# Tractor2000.net
KiCad netlist of a schematic drawn in Altium Designer
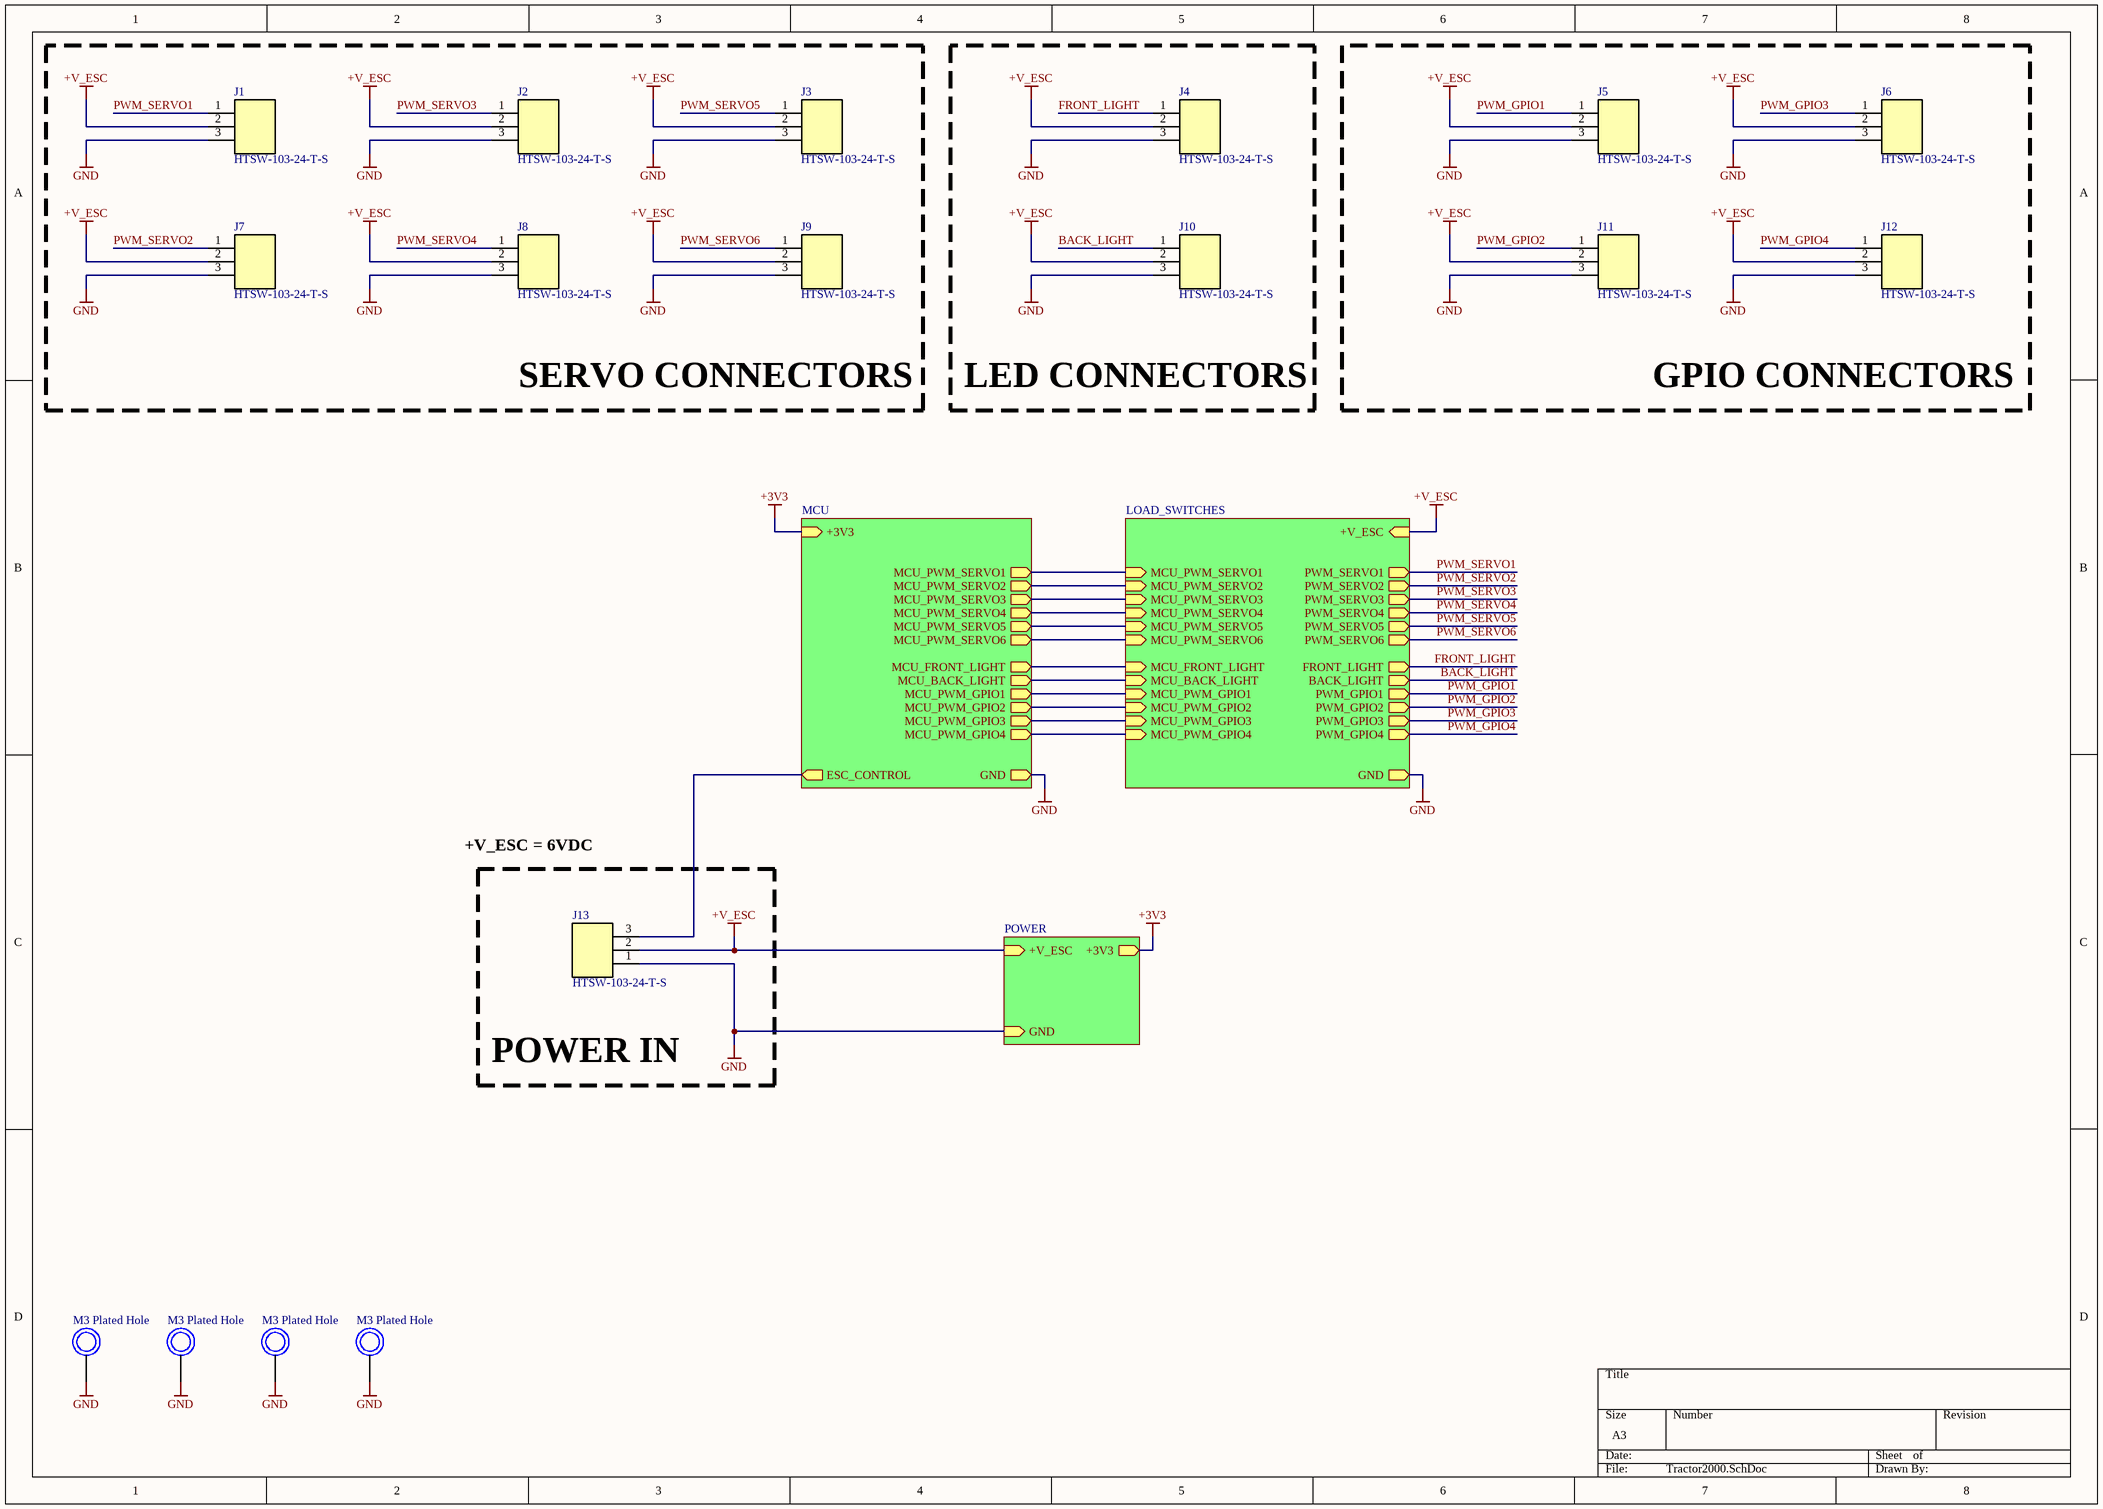
[diagram p0: Tractor2000.SchDoc]

(export (version "E")
  (design (tool "Eeschema 10.0.6"))
  (components
    (comp (ref "J1")
      (value "HTSW-103-24-T-S")
      (footprint "CON3_1X3_TU_TSW_SAI")
      (description "Description")
      (fields (field (name "COPYRIGHT") "Copyright (C) 2026 Ultra Librarian. All rights reserved."))
      (libsource (lib "Tractor2000") (part "HTSW-103-24-T-S"))
    )
    (comp (ref "J2")
      (value "HTSW-103-24-T-S")
      (footprint "CON3_1X3_TU_TSW_SAI")
      (description "Description")
      (fields (field (name "COPYRIGHT") "Copyright (C) 2026 Ultra Librarian. All rights reserved."))
      (libsource (lib "Tractor2000") (part "HTSW-103-24-T-S"))
    )
    (comp (ref "J3")
      (value "HTSW-103-24-T-S")
      (footprint "CON3_1X3_TU_TSW_SAI")
      (description "Description")
      (fields (field (name "COPYRIGHT") "Copyright (C) 2026 Ultra Librarian. All rights reserved."))
      (libsource (lib "Tractor2000") (part "HTSW-103-24-T-S"))
    )
    (comp (ref "J4")
      (value "HTSW-103-24-T-S")
      (footprint "CON3_1X3_TU_TSW_SAI")
      (description "Description")
      (fields (field (name "COPYRIGHT") "Copyright (C) 2026 Ultra Librarian. All rights reserved."))
      (libsource (lib "Tractor2000") (part "HTSW-103-24-T-S"))
    )
    (comp (ref "J5")
      (value "HTSW-103-24-T-S")
      (footprint "CON3_1X3_TU_TSW_SAI")
      (description "Description")
      (fields (field (name "COPYRIGHT") "Copyright (C) 2026 Ultra Librarian. All rights reserved."))
      (libsource (lib "Tractor2000") (part "HTSW-103-24-T-S"))
    )
    (comp (ref "J6")
      (value "HTSW-103-24-T-S")
      (footprint "CON3_1X3_TU_TSW_SAI")
      (description "Description")
      (fields (field (name "COPYRIGHT") "Copyright (C) 2026 Ultra Librarian. All rights reserved."))
      (libsource (lib "Tractor2000") (part "HTSW-103-24-T-S"))
    )
    (comp (ref "J7")
      (value "HTSW-103-24-T-S")
      (footprint "CON3_1X3_TU_TSW_SAI")
      (description "Description")
      (fields (field (name "COPYRIGHT") "Copyright (C) 2026 Ultra Librarian. All rights reserved."))
      (libsource (lib "Tractor2000") (part "HTSW-103-24-T-S"))
    )
    (comp (ref "J8")
      (value "HTSW-103-24-T-S")
      (footprint "CON3_1X3_TU_TSW_SAI")
      (description "Description")
      (fields (field (name "COPYRIGHT") "Copyright (C) 2026 Ultra Librarian. All rights reserved."))
      (libsource (lib "Tractor2000") (part "HTSW-103-24-T-S"))
    )
    (comp (ref "J9")
      (value "HTSW-103-24-T-S")
      (footprint "CON3_1X3_TU_TSW_SAI")
      (description "Description")
      (fields (field (name "COPYRIGHT") "Copyright (C) 2026 Ultra Librarian. All rights reserved."))
      (libsource (lib "Tractor2000") (part "HTSW-103-24-T-S"))
    )
    (comp (ref "J10")
      (value "HTSW-103-24-T-S")
      (footprint "CON3_1X3_TU_TSW_SAI")
      (description "Description")
      (fields (field (name "COPYRIGHT") "Copyright (C) 2026 Ultra Librarian. All rights reserved."))
      (libsource (lib "Tractor2000") (part "HTSW-103-24-T-S"))
    )
    (comp (ref "J11")
      (value "HTSW-103-24-T-S")
      (footprint "CON3_1X3_TU_TSW_SAI")
      (description "Description")
      (fields (field (name "COPYRIGHT") "Copyright (C) 2026 Ultra Librarian. All rights reserved."))
      (libsource (lib "Tractor2000") (part "HTSW-103-24-T-S"))
    )
    (comp (ref "J12")
      (value "HTSW-103-24-T-S")
      (footprint "CON3_1X3_TU_TSW_SAI")
      (description "Description")
      (fields (field (name "COPYRIGHT") "Copyright (C) 2026 Ultra Librarian. All rights reserved."))
      (libsource (lib "Tractor2000") (part "HTSW-103-24-T-S"))
    )
    (comp (ref "J13")
      (value "HTSW-103-24-T-S")
      (footprint "CON3_1X3_TU_TSW_SAI")
      (description "Description")
      (fields (field (name "COPYRIGHT") "Copyright (C) 2026 Ultra Librarian. All rights reserved."))
      (libsource (lib "") (part "HTSW-103-24-T-S_1"))
    )
    (comp (ref "MH1")
      (value "M3 Plated Hole")
      (footprint "M3 Plated Hole")
      (libsource (lib "PolSl Racing - Electrical") (part "Mounting Hole"))
    )
    (comp (ref "MH2")
      (value "M3 Plated Hole")
      (footprint "M3 Plated Hole")
      (libsource (lib "PolSl Racing - Electrical") (part "Mounting Hole"))
    )
    (comp (ref "MH3")
      (value "M3 Plated Hole")
      (footprint "M3 Plated Hole")
      (libsource (lib "PolSl Racing - Electrical") (part "Mounting Hole"))
    )
    (comp (ref "MH4")
      (value "M3 Plated Hole")
      (footprint "M3 Plated Hole")
      (libsource (lib "PolSl Racing - Electrical") (part "Mounting Hole"))
    )
  )
  (nets
    (net (code "2") (name "+V_ESC") (class "Default")
      (node (ref "J1") (pin "2") (pinfunction "2_2") (pintype "passive"))
      (node (ref "J10") (pin "2") (pinfunction "2_2") (pintype "passive"))
      (node (ref "J11") (pin "2") (pinfunction "2_2") (pintype "passive"))
      (node (ref "J12") (pin "2") (pinfunction "2_2") (pintype "passive"))
      (node (ref "J13") (pin "2") (pinfunction "2_2") (pintype "passive"))
      (node (ref "J2") (pin "2") (pinfunction "2_2") (pintype "passive"))
      (node (ref "J3") (pin "2") (pinfunction "2_2") (pintype "passive"))
      (node (ref "J4") (pin "2") (pinfunction "2_2") (pintype "passive"))
      (node (ref "J5") (pin "2") (pinfunction "2_2") (pintype "passive"))
      (node (ref "J6") (pin "2") (pinfunction "2_2") (pintype "passive"))
      (node (ref "J7") (pin "2") (pinfunction "2_2") (pintype "passive"))
      (node (ref "J8") (pin "2") (pinfunction "2_2") (pintype "passive"))
      (node (ref "J9") (pin "2") (pinfunction "2_2") (pintype "passive"))
    )
    (net (code "3") (name "/BACK_LIGHT") (class "Default")
      (node (ref "J10") (pin "1") (pinfunction "1_1") (pintype "passive"))
    )
    (net (code "4") (name "/ESC_CONTROL") (class "Default")
      (node (ref "J13") (pin "3") (pinfunction "3_3") (pintype "passive"))
    )
    (net (code "5") (name "/FRONT_LIGHT") (class "Default")
      (node (ref "J4") (pin "1") (pinfunction "1_1") (pintype "passive"))
    )
    (net (code "18") (name "/PWM_GPIO1") (class "Default")
      (node (ref "J5") (pin "1") (pinfunction "1_1") (pintype "passive"))
    )
    (net (code "19") (name "/PWM_GPIO2") (class "Default")
      (node (ref "J11") (pin "1") (pinfunction "1_1") (pintype "passive"))
    )
    (net (code "20") (name "/PWM_GPIO3") (class "Default")
      (node (ref "J6") (pin "1") (pinfunction "1_1") (pintype "passive"))
    )
    (net (code "21") (name "/PWM_GPIO4") (class "Default")
      (node (ref "J12") (pin "1") (pinfunction "1_1") (pintype "passive"))
    )
    (net (code "22") (name "/PWM_SERVO1") (class "Default")
      (node (ref "J1") (pin "1") (pinfunction "1_1") (pintype "passive"))
    )
    (net (code "23") (name "/PWM_SERVO2") (class "Default")
      (node (ref "J7") (pin "1") (pinfunction "1_1") (pintype "passive"))
    )
    (net (code "24") (name "/PWM_SERVO3") (class "Default")
      (node (ref "J2") (pin "1") (pinfunction "1_1") (pintype "passive"))
    )
    (net (code "25") (name "/PWM_SERVO4") (class "Default")
      (node (ref "J8") (pin "1") (pinfunction "1_1") (pintype "passive"))
    )
    (net (code "26") (name "/PWM_SERVO5") (class "Default")
      (node (ref "J3") (pin "1") (pinfunction "1_1") (pintype "passive"))
    )
    (net (code "27") (name "/PWM_SERVO6") (class "Default")
      (node (ref "J9") (pin "1") (pinfunction "1_1") (pintype "passive"))
    )
    (net (code "28") (name "GND") (class "Default")
      (node (ref "J1") (pin "3") (pinfunction "3_3") (pintype "passive"))
      (node (ref "J10") (pin "3") (pinfunction "3_3") (pintype "passive"))
      (node (ref "J11") (pin "3") (pinfunction "3_3") (pintype "passive"))
      (node (ref "J12") (pin "3") (pinfunction "3_3") (pintype "passive"))
      (node (ref "J13") (pin "1") (pinfunction "1_1") (pintype "passive"))
      (node (ref "J2") (pin "3") (pinfunction "3_3") (pintype "passive"))
      (node (ref "J3") (pin "3") (pinfunction "3_3") (pintype "passive"))
      (node (ref "J4") (pin "3") (pinfunction "3_3") (pintype "passive"))
      (node (ref "J5") (pin "3") (pinfunction "3_3") (pintype "passive"))
      (node (ref "J6") (pin "3") (pinfunction "3_3") (pintype "passive"))
      (node (ref "J7") (pin "3") (pinfunction "3_3") (pintype "passive"))
      (node (ref "J8") (pin "3") (pinfunction "3_3") (pintype "passive"))
      (node (ref "J9") (pin "3") (pinfunction "3_3") (pintype "passive"))
      (node (ref "MH1") (pin "1") (pinfunction "1_1") (pintype "passive"))
      (node (ref "MH2") (pin "1") (pinfunction "1_1") (pintype "passive"))
      (node (ref "MH3") (pin "1") (pinfunction "1_1") (pintype "passive"))
      (node (ref "MH4") (pin "1") (pinfunction "1_1") (pintype "passive"))
    )
  )
)
